# WL-DAC904.net
KiCad netlist of a schematic drawn in Altium Designer
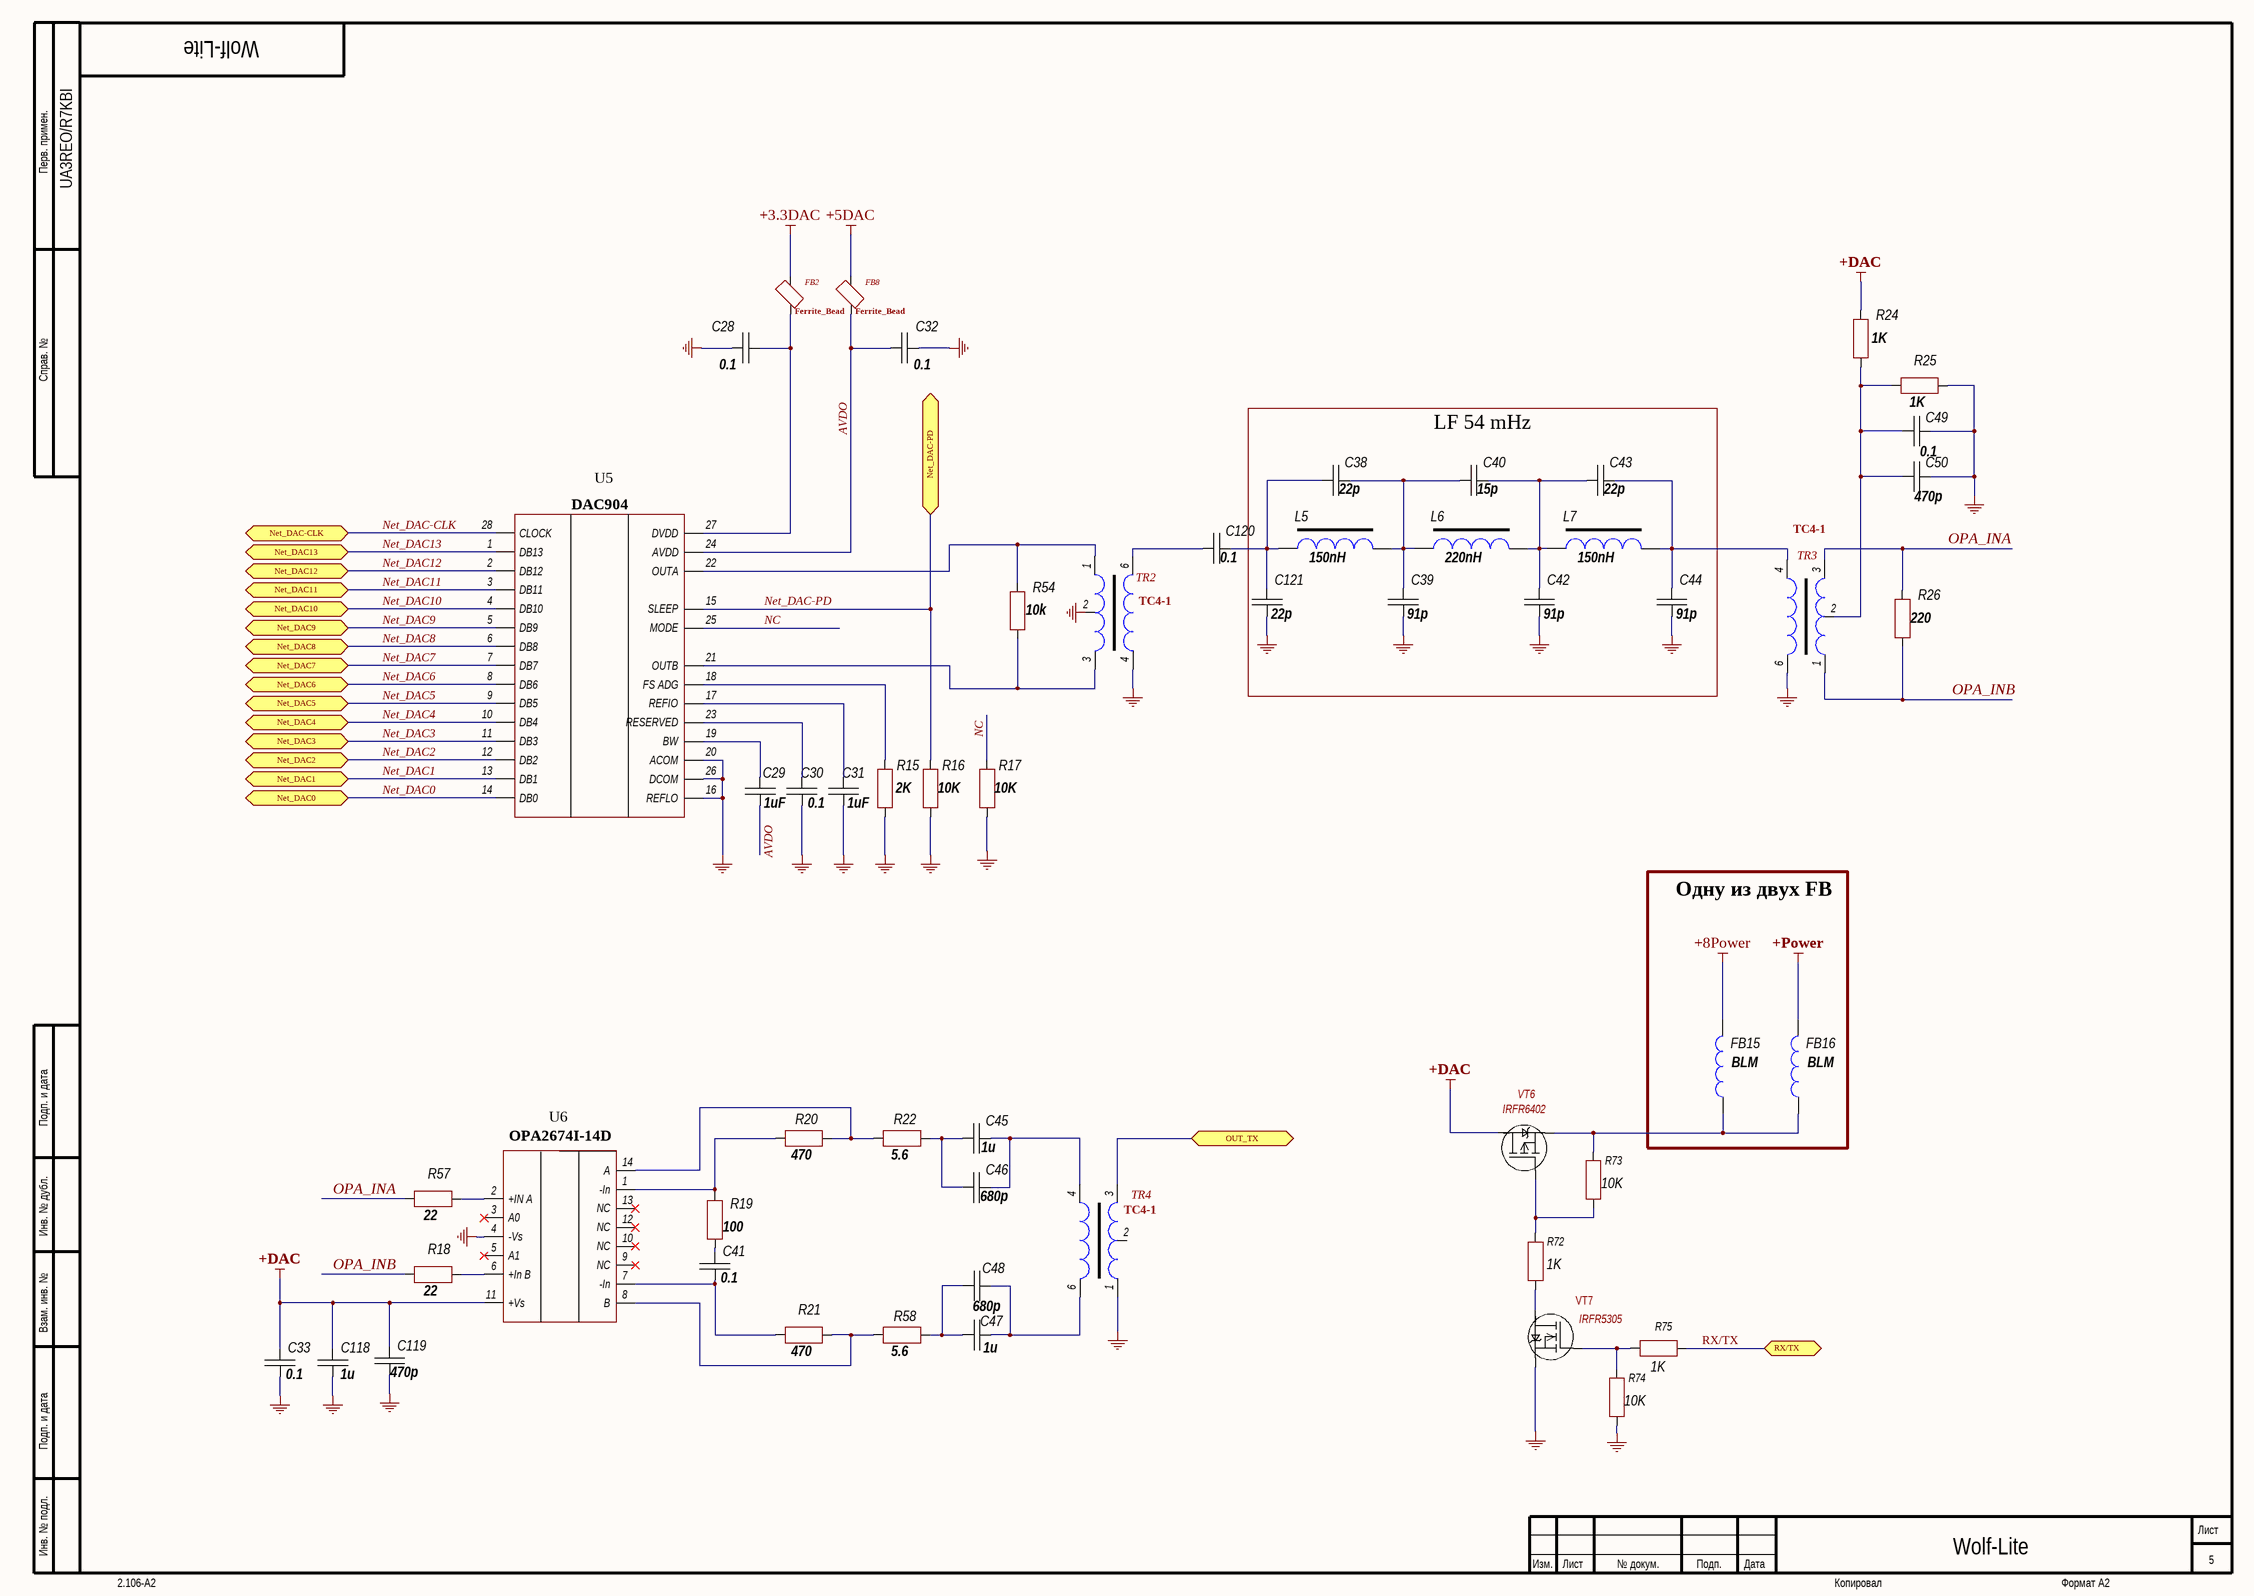
[diagram p0: WL-DAC904.SchDoc]

(export (version "E")
  (design (tool "Eeschema 10.0.6"))
  (components
    (comp (ref "C28")
      (value "0.1")
      (footprint "standard:CH0805C")
      (libsource (lib "Discrete") (part "Capacitor"))
    )
    (comp (ref "C29")
      (value "1uF")
      (footprint "standard:CH0805C")
      (libsource (lib "Discrete") (part "Capacitor"))
    )
    (comp (ref "C30")
      (value "0.1")
      (footprint "standard:CH0805C")
      (libsource (lib "Discrete") (part "Capacitor"))
    )
    (comp (ref "C31")
      (value "1uF")
      (footprint "standard:CH0805C")
      (libsource (lib "Discrete") (part "Capacitor"))
    )
    (comp (ref "C32")
      (value "0.1")
      (footprint "standard:CH0805C")
      (libsource (lib "Discrete") (part "Capacitor"))
    )
    (comp (ref "C33")
      (value "0.1")
      (footprint "standard:CH0805C")
      (libsource (lib "Discrete") (part "Capacitor"))
    )
    (comp (ref "C38")
      (value "22p")
      (footprint "standard:CH0805C")
      (libsource (lib "Discrete") (part "Capacitor"))
    )
    (comp (ref "C39")
      (value "91p")
      (footprint "standard:CH0805C")
      (libsource (lib "Discrete") (part "Capacitor"))
    )
    (comp (ref "C40")
      (value "15p")
      (footprint "standard:CH0805C")
      (libsource (lib "Discrete") (part "Capacitor"))
    )
    (comp (ref "C41")
      (value "0.1")
      (footprint "standard:CH0805C")
      (libsource (lib "Discrete") (part "Capacitor"))
    )
    (comp (ref "C42")
      (value "91p")
      (footprint "standard:CH0805C")
      (libsource (lib "Discrete") (part "Capacitor"))
    )
    (comp (ref "C43")
      (value "22p")
      (footprint "standard:CH0805C")
      (libsource (lib "Discrete") (part "Capacitor"))
    )
    (comp (ref "C44")
      (value "91p")
      (footprint "standard:CH0805C")
      (libsource (lib "Discrete") (part "Capacitor"))
    )
    (comp (ref "C45")
      (value "1u")
      (footprint "standard:CH0805C")
      (libsource (lib "Discrete") (part "Capacitor"))
    )
    (comp (ref "C46")
      (value "680p")
      (footprint "standard:CH0805C")
      (libsource (lib "Discrete") (part "Capacitor"))
    )
    (comp (ref "C47")
      (value "1u")
      (footprint "standard:CH0805C")
      (libsource (lib "Discrete") (part "Capacitor"))
    )
    (comp (ref "C48")
      (value "680p")
      (footprint "standard:CH0805C")
      (libsource (lib "Discrete") (part "Capacitor"))
    )
    (comp (ref "C49")
      (value "0.1")
      (footprint "standard:CH0805C")
      (libsource (lib "Discrete") (part "Capacitor"))
    )
    (comp (ref "C50")
      (value "470p")
      (footprint "standard:CH0805C")
      (libsource (lib "Discrete") (part "Capacitor"))
    )
    (comp (ref "C118")
      (value "1u")
      (footprint "standard:CH0805C")
      (libsource (lib "Discrete") (part "Capacitor"))
    )
    (comp (ref "C119")
      (value "470p")
      (footprint "standard:CH0805C")
      (libsource (lib "Discrete") (part "Capacitor"))
    )
    (comp (ref "C120")
      (value "0.1")
      (footprint "standard:CH0805C")
      (libsource (lib "Discrete") (part "Capacitor"))
    )
    (comp (ref "C121")
      (value "22p")
      (footprint "standard:CH0805C")
      (libsource (lib "Discrete") (part "Capacitor"))
    )
    (comp (ref "FB2") (value "Ferrite_Bead") (footprint "CH0805L") (libsource (lib "Discrete") (part "FB")))
    (comp (ref "FB8") (value "Ferrite_Bead") (footprint "CH0805L") (libsource (lib "Discrete") (part "FB")))
    (comp (ref "FB15")
      (value "BLM")
      (footprint "standard:CH0805L")
      (libsource (lib "Discrete") (part "Inductor"))
    )
    (comp (ref "FB16")
      (value "BLM")
      (footprint "standard:CH0805L")
      (libsource (lib "Discrete") (part "Inductor"))
    )
    (comp (ref "L5") (value "150nH") (footprint "L1210") (libsource (lib "Transformers") (part "TRANS")))
    (comp (ref "L6") (value "220nH") (footprint "L1210") (libsource (lib "Transformers") (part "TRANS")))
    (comp (ref "L7") (value "150nH") (footprint "L1210") (libsource (lib "Transformers") (part "TRANS")))
    (comp (ref "R15") (value "2K") (footprint "standard:CH0805R") (libsource (lib "") (part "Resistor_2")))
    (comp (ref "R16") (value "10K") (footprint "standard:CH0805R") (libsource (lib "") (part "Resistor_2")))
    (comp (ref "R17") (value "10K") (footprint "standard:CH0805R") (libsource (lib "") (part "Resistor_2")))
    (comp (ref "R18")
      (value "22")
      (footprint "standard:CH0805R")
      (libsource (lib "Discrete") (part "Resistor"))
    )
    (comp (ref "R19") (value "100") (footprint "standard:CH0805R") (libsource (lib "") (part "Resistor_2")))
    (comp (ref "R20")
      (value "470")
      (footprint "standard:CH0805R")
      (libsource (lib "Discrete") (part "Resistor"))
    )
    (comp (ref "R21")
      (value "470")
      (footprint "standard:CH0805R")
      (libsource (lib "Discrete") (part "Resistor"))
    )
    (comp (ref "R22")
      (value "5.6")
      (footprint "standard:CH0805R")
      (libsource (lib "Discrete") (part "Resistor"))
    )
    (comp (ref "R24") (value "1K") (footprint "standard:CH0805R") (libsource (lib "") (part "Resistor_1")))
    (comp (ref "R25")
      (value "1K")
      (footprint "standard:CH0805R")
      (libsource (lib "Discrete") (part "Resistor"))
    )
    (comp (ref "R26") (value "220") (footprint "standard:CH0805R") (libsource (lib "") (part "Resistor_1")))
    (comp (ref "R54") (value "10k") (footprint "standard:CH0805R") (libsource (lib "") (part "Resistor_1")))
    (comp (ref "R57")
      (value "22")
      (footprint "standard:CH0805R")
      (libsource (lib "Discrete") (part "Resistor"))
    )
    (comp (ref "R58")
      (value "5.6")
      (footprint "standard:CH0805R")
      (libsource (lib "Discrete") (part "Resistor"))
    )
    (comp (ref "R72") (value "1K") (footprint "standard:CH0805R") (libsource (lib "") (part "Resistor_2")))
    (comp (ref "R73") (value "10K") (footprint "standard:CH0805R") (libsource (lib "") (part "Resistor_2")))
    (comp (ref "R74") (value "10K") (footprint "standard:CH0805R") (libsource (lib "") (part "Resistor_2")))
    (comp (ref "R75") (value "1K") (footprint "standard:CH0805R") (libsource (lib "") (part "Resistor_3")))
    (comp (ref "TR2") (value "TC4-1") (footprint "TC1-4") (libsource (lib "") (part "TC4-1_1")))
    (comp (ref "TR3") (value "TC4-1") (footprint "TC1-4") (libsource (lib "Transformers") (part "TC4-1")))
    (comp (ref "TR4") (value "TC4-1") (footprint "TC1-4") (libsource (lib "Transformers") (part "TC4-1")))
    (comp (ref "U5") (value "DAC904") (footprint "28-TSSOP") (libsource (lib "Digital") (part "DAC904")))
    (comp (ref "U6")
      (value "OPA2674I-14D")
      (footprint "14-SOIC")
      (libsource (lib "Digital") (part "OPA2674"))
    )
    (comp (ref "VT6")
      (value "IRFR6402")
      (footprint "SOT23_132")
      (libsource (lib "Transistor") (part "P-KANAL"))
    )
    (comp (ref "VT7")
      (value "IRFR5305")
      (footprint "SOT23_132")
      (libsource (lib "Transistor") (part "N-KANAL"))
    )
  )
  (nets
    (net (code "1") (name "+3.3DAC") (class "Default")
      (node (ref "FB2") (pin "2") (pinfunction "2_2") (pintype "passive"))
    )
    (net (code "2") (name "+5DAC") (class "Default")
      (node (ref "FB8") (pin "2") (pinfunction "2_2") (pintype "passive"))
    )
    (net (code "3") (name "+8Power") (class "Default")
      (node (ref "FB15") (pin "1") (pinfunction "1_1") (pintype "passive"))
    )
    (net (code "4") (name "+DAC") (class "Default")
      (node (ref "C118") (pin "1") (pinfunction "1_1") (pintype "power_in"))
      (node (ref "C119") (pin "1") (pinfunction "1_1") (pintype "power_in"))
      (node (ref "C33") (pin "1") (pinfunction "1_1") (pintype "power_in"))
      (node (ref "R24") (pin "1") (pinfunction "1_1") (pintype "passive"))
      (node (ref "U6") (pin "11") (pinfunction "+Vs_11") (pintype "passive"))
      (node (ref "VT6") (pin "3") (pinfunction "Сток(Drain)_3") (pintype "passive"))
    )
    (net (code "5") (name "+Power") (class "Default")
      (node (ref "FB16") (pin "1") (pinfunction "1_1") (pintype "passive"))
    )
    (net (code "6") (name "/AVDO") (class "Default")
      (node (ref "C29") (pin "2") (pinfunction "2_2") (pintype "power_in"))
      (node (ref "C32") (pin "1") (pinfunction "1_1") (pintype "power_in"))
      (node (ref "FB8") (pin "1") (pinfunction "1_1") (pintype "passive"))
      (node (ref "U5") (pin "24") (pinfunction "AVDD_24") (pintype "passive"))
    )
    (net (code "7") (name "/NC") (class "Default")
      (node (ref "R17") (pin "2") (pinfunction "2_2") (pintype "passive"))
      (node (ref "U5") (pin "25") (pinfunction "MODE_25") (pintype "passive"))
    )
    (net (code "8") (name "/Net_DAC-CLK") (class "Default")
      (node (ref "U5") (pin "28") (pinfunction "CLOCK_28") (pintype "passive"))
    )
    (net (code "9") (name "/Net_DAC-PD") (class "Default")
      (node (ref "R16") (pin "2") (pinfunction "2_2") (pintype "passive"))
      (node (ref "U5") (pin "15") (pinfunction "SLEEP_15") (pintype "passive"))
    )
    (net (code "10") (name "/Net_DAC0") (class "Default")
      (node (ref "U5") (pin "14") (pinfunction "DB0_14") (pintype "power_in"))
    )
    (net (code "11") (name "/Net_DAC1") (class "Default")
      (node (ref "U5") (pin "13") (pinfunction "DB1_13") (pintype "power_in"))
    )
    (net (code "12") (name "/Net_DAC2") (class "Default")
      (node (ref "U5") (pin "12") (pinfunction "DB2_12") (pintype "power_in"))
    )
    (net (code "13") (name "/Net_DAC3") (class "Default")
      (node (ref "U5") (pin "11") (pinfunction "DB3_11") (pintype "power_in"))
    )
    (net (code "14") (name "/Net_DAC4") (class "Default")
      (node (ref "U5") (pin "10") (pinfunction "DB4_10") (pintype "power_in"))
    )
    (net (code "15") (name "/Net_DAC5") (class "Default")
      (node (ref "U5") (pin "9") (pinfunction "DB5_9") (pintype "power_in"))
    )
    (net (code "16") (name "/Net_DAC6") (class "Default")
      (node (ref "U5") (pin "8") (pinfunction "DB6_8") (pintype "power_in"))
    )
    (net (code "17") (name "/Net_DAC7") (class "Default")
      (node (ref "U5") (pin "7") (pinfunction "DB7_7") (pintype "power_in"))
    )
    (net (code "18") (name "/Net_DAC8") (class "Default")
      (node (ref "U5") (pin "6") (pinfunction "DB8_6") (pintype "power_in"))
    )
    (net (code "19") (name "/Net_DAC9") (class "Default")
      (node (ref "U5") (pin "5") (pinfunction "DB9_5") (pintype "power_in"))
    )
    (net (code "20") (name "/Net_DAC10") (class "Default")
      (node (ref "U5") (pin "4") (pinfunction "DB10_4") (pintype "power_in"))
    )
    (net (code "21") (name "/Net_DAC11") (class "Default")
      (node (ref "U5") (pin "3") (pinfunction "DB11_3") (pintype "power_in"))
    )
    (net (code "22") (name "/Net_DAC12") (class "Default")
      (node (ref "U5") (pin "2") (pinfunction "DB12_2") (pintype "power_in"))
    )
    (net (code "23") (name "/Net_DAC13") (class "Default")
      (node (ref "U5") (pin "1") (pinfunction "DB13_1") (pintype "power_in"))
    )
    (net (code "24") (name "/OPA_INA") (class "Default")
      (node (ref "R26") (pin "1") (pinfunction "1_1") (pintype "passive"))
      (node (ref "R57") (pin "1") (pinfunction "1_1") (pintype "passive"))
      (node (ref "TR3") (pin "3") (pinfunction "3_3") (pintype "power_in"))
    )
    (net (code "25") (name "/OPA_INB") (class "Default")
      (node (ref "R18") (pin "1") (pinfunction "1_1") (pintype "passive"))
      (node (ref "R26") (pin "2") (pinfunction "2_2") (pintype "passive"))
      (node (ref "TR3") (pin "1") (pinfunction "1_1") (pintype "power_in"))
    )
    (net (code "26") (name "/OUT_TX") (class "Default")
      (node (ref "TR4") (pin "3") (pinfunction "3_3") (pintype "power_in"))
    )
    (net (code "27") (name "/RX{slash}TX") (class "Default")
      (node (ref "R75") (pin "1") (pinfunction "1_1") (pintype "passive"))
    )
    (net (code "28") (name "GND") (class "Default")
      (node (ref "C118") (pin "2") (pinfunction "2_2") (pintype "power_in"))
      (node (ref "C119") (pin "2") (pinfunction "2_2") (pintype "power_in"))
      (node (ref "C121") (pin "1") (pinfunction "1_1") (pintype "power_in"))
      (node (ref "C28") (pin "2") (pinfunction "2_2") (pintype "power_in"))
      (node (ref "C30") (pin "2") (pinfunction "2_2") (pintype "power_in"))
      (node (ref "C31") (pin "2") (pinfunction "2_2") (pintype "power_in"))
      (node (ref "C32") (pin "2") (pinfunction "2_2") (pintype "power_in"))
      (node (ref "C33") (pin "2") (pinfunction "2_2") (pintype "power_in"))
      (node (ref "C39") (pin "1") (pinfunction "1_1") (pintype "power_in"))
      (node (ref "C42") (pin "1") (pinfunction "1_1") (pintype "power_in"))
      (node (ref "C44") (pin "1") (pinfunction "1_1") (pintype "power_in"))
      (node (ref "C49") (pin "1") (pinfunction "1_1") (pintype "power_in"))
      (node (ref "C50") (pin "1") (pinfunction "1_1") (pintype "power_in"))
      (node (ref "R15") (pin "1") (pinfunction "1_1") (pintype "passive"))
      (node (ref "R16") (pin "1") (pinfunction "1_1") (pintype "passive"))
      (node (ref "R17") (pin "1") (pinfunction "1_1") (pintype "passive"))
      (node (ref "R25") (pin "2") (pinfunction "2_2") (pintype "passive"))
      (node (ref "R74") (pin "1") (pinfunction "1_1") (pintype "passive"))
      (node (ref "TR2") (pin "2") (pinfunction "2_2") (pintype "power_in"))
      (node (ref "TR2") (pin "4") (pinfunction "4_4") (pintype "power_in"))
      (node (ref "TR3") (pin "6") (pinfunction "6_6") (pintype "power_in"))
      (node (ref "TR4") (pin "1") (pinfunction "1_1") (pintype "power_in"))
      (node (ref "U5") (pin "16") (pinfunction "REFLO_16") (pintype "passive"))
      (node (ref "U5") (pin "20") (pinfunction "ACOM_20") (pintype "passive"))
      (node (ref "U5") (pin "26") (pinfunction "DCOM_26") (pintype "passive"))
      (node (ref "U6") (pin "4") (pinfunction "-Vs_4") (pintype "passive"))
      (node (ref "VT7") (pin "2") (pinfunction "I_2") (pintype "passive"))
    )
    (net (code "29") (name "Net-(C38-Pad2)") (class "Default")
      (node (ref "C38") (pin "2") (pinfunction "2_2") (pintype "power_in"))
      (node (ref "C39") (pin "2") (pinfunction "2_2") (pintype "power_in"))
      (node (ref "C40") (pin "1") (pinfunction "1_1") (pintype "power_in"))
      (node (ref "L5") (pin "2") (pinfunction "2_2") (pintype "power_in"))
      (node (ref "L6") (pin "1") (pinfunction "1_1") (pintype "power_in"))
    )
    (net (code "30") (name "Net-(C40-Pad2)") (class "Default")
      (node (ref "C40") (pin "2") (pinfunction "2_2") (pintype "power_in"))
      (node (ref "C42") (pin "2") (pinfunction "2_2") (pintype "power_in"))
      (node (ref "C43") (pin "1") (pinfunction "1_1") (pintype "power_in"))
      (node (ref "L6") (pin "2") (pinfunction "2_2") (pintype "power_in"))
      (node (ref "L7") (pin "1") (pinfunction "1_1") (pintype "power_in"))
    )
    (net (code "31") (name "Net-(C41-Pad1)") (class "Default")
      (node (ref "C41") (pin "1") (pinfunction "1_1") (pintype "power_in"))
      (node (ref "R19") (pin "1") (pinfunction "1_1") (pintype "passive"))
    )
    (net (code "32") (name "Net-(C41-Pad2)") (class "Default")
      (node (ref "C41") (pin "2") (pinfunction "2_2") (pintype "power_in"))
      (node (ref "R21") (pin "1") (pinfunction "1_1") (pintype "passive"))
      (node (ref "U6") (pin "7") (pinfunction "-In_7") (pintype "passive"))
    )
    (net (code "33") (name "Net-(C43-Pad2)") (class "Default")
      (node (ref "C43") (pin "2") (pinfunction "2_2") (pintype "power_in"))
      (node (ref "C44") (pin "2") (pinfunction "2_2") (pintype "power_in"))
      (node (ref "L7") (pin "2") (pinfunction "2_2") (pintype "power_in"))
      (node (ref "TR3") (pin "4") (pinfunction "4_4") (pintype "power_in"))
    )
    (net (code "34") (name "Net-(C45-Pad1)") (class "Default")
      (node (ref "C45") (pin "1") (pinfunction "1_1") (pintype "power_in"))
      (node (ref "C46") (pin "1") (pinfunction "1_1") (pintype "power_in"))
      (node (ref "R22") (pin "2") (pinfunction "2_2") (pintype "passive"))
    )
    (net (code "35") (name "Net-(C45-Pad2)") (class "Default")
      (node (ref "C45") (pin "2") (pinfunction "2_2") (pintype "power_in"))
      (node (ref "C46") (pin "2") (pinfunction "2_2") (pintype "power_in"))
      (node (ref "TR4") (pin "4") (pinfunction "4_4") (pintype "power_in"))
    )
    (net (code "36") (name "Net-(C47-Pad1)") (class "Default")
      (node (ref "C47") (pin "1") (pinfunction "1_1") (pintype "power_in"))
      (node (ref "C48") (pin "1") (pinfunction "1_1") (pintype "power_in"))
      (node (ref "R58") (pin "2") (pinfunction "2_2") (pintype "passive"))
    )
    (net (code "37") (name "Net-(C47-Pad2)") (class "Default")
      (node (ref "C47") (pin "2") (pinfunction "2_2") (pintype "power_in"))
      (node (ref "C48") (pin "2") (pinfunction "2_2") (pintype "power_in"))
      (node (ref "TR4") (pin "6") (pinfunction "6_6") (pintype "power_in"))
    )
    (net (code "38") (name "Net-(C49-Pad2)") (class "Default")
      (node (ref "C49") (pin "2") (pinfunction "2_2") (pintype "power_in"))
      (node (ref "C50") (pin "2") (pinfunction "2_2") (pintype "power_in"))
      (node (ref "R24") (pin "2") (pinfunction "2_2") (pintype "passive"))
      (node (ref "R25") (pin "1") (pinfunction "1_1") (pintype "passive"))
      (node (ref "TR3") (pin "2") (pinfunction "2_2") (pintype "power_in"))
    )
    (net (code "39") (name "Net-(C120-Pad1)") (class "Default")
      (node (ref "C120") (pin "1") (pinfunction "1_1") (pintype "power_in"))
      (node (ref "TR2") (pin "6") (pinfunction "6_6") (pintype "power_in"))
    )
    (net (code "40") (name "Net-(C120-Pad2)") (class "Default")
      (node (ref "C120") (pin "2") (pinfunction "2_2") (pintype "power_in"))
      (node (ref "C121") (pin "2") (pinfunction "2_2") (pintype "power_in"))
      (node (ref "C38") (pin "1") (pinfunction "1_1") (pintype "power_in"))
      (node (ref "L5") (pin "1") (pinfunction "1_1") (pintype "power_in"))
    )
    (net (code "41") (name "Net-(R19-Pad2)") (class "Default")
      (node (ref "R19") (pin "2") (pinfunction "2_2") (pintype "passive"))
      (node (ref "R20") (pin "1") (pinfunction "1_1") (pintype "passive"))
      (node (ref "U6") (pin "1") (pinfunction "-In_1") (pintype "passive"))
    )
    (net (code "42") (name "Net-(U5-BW)") (class "Default")
      (node (ref "C29") (pin "1") (pinfunction "1_1") (pintype "power_in"))
      (node (ref "U5") (pin "19") (pinfunction "BW_19") (pintype "passive"))
    )
    (net (code "43") (name "Net-(U5-DVDD)") (class "Default")
      (node (ref "C28") (pin "1") (pinfunction "1_1") (pintype "power_in"))
      (node (ref "FB2") (pin "1") (pinfunction "1_1") (pintype "passive"))
      (node (ref "U5") (pin "27") (pinfunction "DVDD_27") (pintype "passive"))
    )
    (net (code "44") (name "Net-(U5-FS_ADG)") (class "Default")
      (node (ref "R15") (pin "2") (pinfunction "2_2") (pintype "passive"))
      (node (ref "U5") (pin "18") (pinfunction "FS_ADG_18") (pintype "passive"))
    )
    (net (code "45") (name "Net-(U5-OUTA)") (class "Default")
      (node (ref "R54") (pin "1") (pinfunction "1_1") (pintype "passive"))
      (node (ref "TR2") (pin "1") (pinfunction "1_1") (pintype "power_in"))
      (node (ref "U5") (pin "22") (pinfunction "OUTA_22") (pintype "passive"))
    )
    (net (code "46") (name "Net-(U5-OUTB)") (class "Default")
      (node (ref "R54") (pin "2") (pinfunction "2_2") (pintype "passive"))
      (node (ref "TR2") (pin "3") (pinfunction "3_3") (pintype "power_in"))
      (node (ref "U5") (pin "21") (pinfunction "OUTB_21") (pintype "passive"))
    )
    (net (code "47") (name "Net-(U5-REFIO)") (class "Default")
      (node (ref "C31") (pin "1") (pinfunction "1_1") (pintype "power_in"))
      (node (ref "U5") (pin "17") (pinfunction "REFIO_17") (pintype "passive"))
    )
    (net (code "48") (name "Net-(U5-RESERVED)") (class "Default")
      (node (ref "C30") (pin "1") (pinfunction "1_1") (pintype "power_in"))
      (node (ref "U5") (pin "23") (pinfunction "RESERVED_23") (pintype "passive"))
    )
    (net (code "49") (name "Net-(U6-+IN_A)") (class "Default")
      (node (ref "R57") (pin "2") (pinfunction "2_2") (pintype "passive"))
      (node (ref "U6") (pin "2") (pinfunction "+IN_A_2") (pintype "passive"))
    )
    (net (code "50") (name "Net-(U6-+In_B)") (class "Default")
      (node (ref "R18") (pin "2") (pinfunction "2_2") (pintype "passive"))
      (node (ref "U6") (pin "6") (pinfunction "+In_B_6") (pintype "passive"))
    )
    (net (code "51") (name "Net-(U6-A)") (class "Default")
      (node (ref "R20") (pin "2") (pinfunction "2_2") (pintype "passive"))
      (node (ref "R22") (pin "1") (pinfunction "1_1") (pintype "passive"))
      (node (ref "U6") (pin "14") (pinfunction "A_14") (pintype "passive"))
    )
    (net (code "52") (name "Net-(U6-B)") (class "Default")
      (node (ref "R21") (pin "2") (pinfunction "2_2") (pintype "passive"))
      (node (ref "R58") (pin "1") (pinfunction "1_1") (pintype "passive"))
      (node (ref "U6") (pin "8") (pinfunction "B_8") (pintype "passive"))
    )
    (net (code "53") (name "Net-(VT6-I)") (class "Default")
      (node (ref "FB15") (pin "2") (pinfunction "2_2") (pintype "passive"))
      (node (ref "FB16") (pin "2") (pinfunction "2_2") (pintype "passive"))
      (node (ref "R73") (pin "2") (pinfunction "2_2") (pintype "passive"))
      (node (ref "VT6") (pin "2") (pinfunction "I_2") (pintype "passive"))
    )
    (net (code "54") (name "Net-(VT6-Затвор(Gate))") (class "Default")
      (node (ref "R72") (pin "2") (pinfunction "2_2") (pintype "passive"))
      (node (ref "R73") (pin "1") (pinfunction "1_1") (pintype "passive"))
      (node (ref "VT6") (pin "1") (pinfunction "Затвор(Gate)_1") (pintype "passive"))
    )
    (net (code "55") (name "Net-(VT7-Затвор(Gate))") (class "Default")
      (node (ref "R74") (pin "2") (pinfunction "2_2") (pintype "passive"))
      (node (ref "R75") (pin "2") (pinfunction "2_2") (pintype "passive"))
      (node (ref "VT7") (pin "1") (pinfunction "Затвор(Gate)_1") (pintype "passive"))
    )
    (net (code "56") (name "Net-(VT7-Сток(Drain))") (class "Default")
      (node (ref "R72") (pin "1") (pinfunction "1_1") (pintype "passive"))
      (node (ref "VT7") (pin "3") (pinfunction "Сток(Drain)_3") (pintype "passive"))
    )
    (net (code "57") (name "unconnected-(TR4-Pad2)") (class "Default")
      (node (ref "TR4") (pin "2") (pinfunction "2_2") (pintype "power_in"))
    )
    (net (code "58") (name "unconnected-(U6-A0-Pad3)") (class "Default")
      (node (ref "U6") (pin "3") (pinfunction "A0_3") (pintype "passive+no_connect"))
    )
    (net (code "59") (name "unconnected-(U6-A1-Pad5)") (class "Default")
      (node (ref "U6") (pin "5") (pinfunction "A1_5") (pintype "passive+no_connect"))
    )
    (net (code "60") (name "unconnected-(U6-NC-Pad9)") (class "Default")
      (node (ref "U6") (pin "9") (pinfunction "NC_9") (pintype "passive+no_connect"))
    )
    (net (code "61") (name "unconnected-(U6-NC-Pad10)") (class "Default")
      (node (ref "U6") (pin "10") (pinfunction "NC_10") (pintype "passive+no_connect"))
    )
    (net (code "62") (name "unconnected-(U6-NC-Pad12)") (class "Default")
      (node (ref "U6") (pin "12") (pinfunction "NC_12") (pintype "passive+no_connect"))
    )
    (net (code "63") (name "unconnected-(U6-NC-Pad13)") (class "Default")
      (node (ref "U6") (pin "13") (pinfunction "NC_13") (pintype "passive+no_connect"))
    )
  )
)
